# Optocoupler_module.net
KiCad netlist of a schematic drawn in Altium Designer
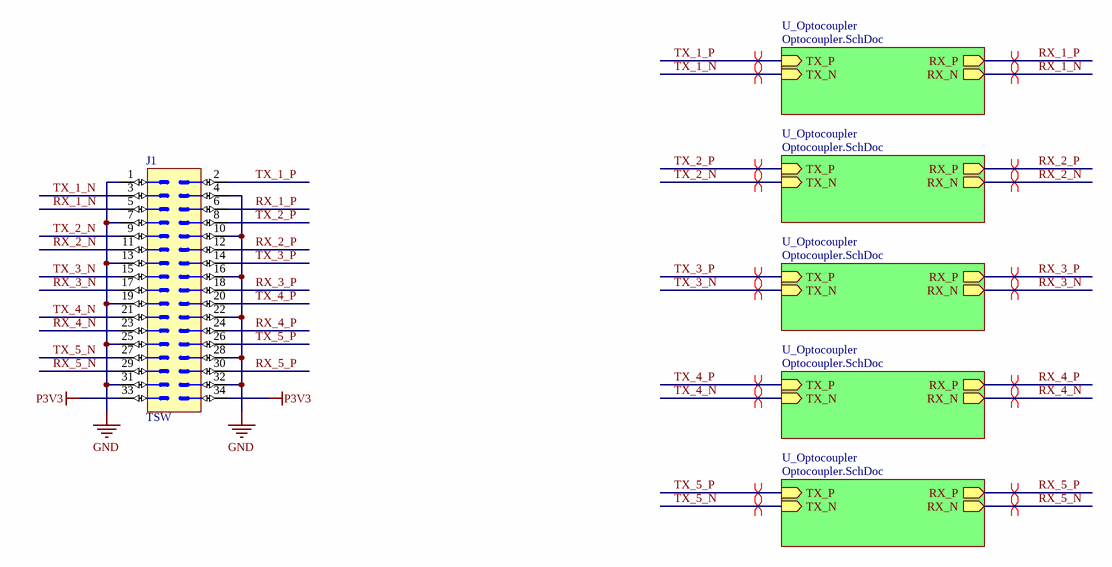
[diagram p0: Optocoupler_module.SchDoc]

(export (version "E")
  (design (tool "Eeschema 10.0.6"))
  (components
    (comp (ref "J1")
      (value "TSW")
      (footprint "SAMTEC_SW-117-08")
      (description "Connector 34 Male")
      (fields
        (field (name "PART NUMBER") "TSW-117-08-T-D-RA")
        (field (name "MANUFACTURER") "SAMTEC")
        (field (name "AUTHOR") "Michal Beldyga")
      )
      (libsource (lib "Connectors") (part "Connector 34 Male 2 Row"))
    )
  )
  (nets
    (net (code "1") (name "/RX_1_N") (class "Default")
      (node (ref "J1") (pin "5") (pinfunction "5_5") (pintype "bidirectional"))
    )
    (net (code "2") (name "/RX_1_P") (class "Default")
      (node (ref "J1") (pin "6") (pinfunction "6_6") (pintype "bidirectional"))
    )
    (net (code "3") (name "/RX_2_N") (class "Default")
      (node (ref "J1") (pin "11") (pinfunction "11_11") (pintype "bidirectional"))
    )
    (net (code "4") (name "/RX_2_P") (class "Default")
      (node (ref "J1") (pin "12") (pinfunction "12_12") (pintype "bidirectional"))
    )
    (net (code "5") (name "/RX_3_N") (class "Default")
      (node (ref "J1") (pin "17") (pinfunction "17_17") (pintype "bidirectional"))
    )
    (net (code "6") (name "/RX_3_P") (class "Default")
      (node (ref "J1") (pin "18") (pinfunction "18_18") (pintype "bidirectional"))
    )
    (net (code "7") (name "/RX_4_N") (class "Default")
      (node (ref "J1") (pin "23") (pinfunction "23_23") (pintype "bidirectional"))
    )
    (net (code "8") (name "/RX_4_P") (class "Default")
      (node (ref "J1") (pin "24") (pinfunction "24_24") (pintype "bidirectional"))
    )
    (net (code "9") (name "/RX_5_N") (class "Default")
      (node (ref "J1") (pin "29") (pinfunction "29_29") (pintype "bidirectional"))
    )
    (net (code "10") (name "/RX_5_P") (class "Default")
      (node (ref "J1") (pin "30") (pinfunction "30_30") (pintype "bidirectional"))
    )
    (net (code "11") (name "/TX_1_N") (class "Default")
      (node (ref "J1") (pin "3") (pinfunction "3_3") (pintype "bidirectional"))
    )
    (net (code "12") (name "/TX_1_P") (class "Default")
      (node (ref "J1") (pin "2") (pinfunction "2_2") (pintype "bidirectional"))
    )
    (net (code "13") (name "/TX_2_N") (class "Default")
      (node (ref "J1") (pin "9") (pinfunction "9_9") (pintype "bidirectional"))
    )
    (net (code "14") (name "/TX_2_P") (class "Default")
      (node (ref "J1") (pin "8") (pinfunction "8_8") (pintype "bidirectional"))
    )
    (net (code "15") (name "/TX_3_N") (class "Default")
      (node (ref "J1") (pin "15") (pinfunction "15_15") (pintype "bidirectional"))
    )
    (net (code "16") (name "/TX_3_P") (class "Default")
      (node (ref "J1") (pin "14") (pinfunction "14_14") (pintype "bidirectional"))
    )
    (net (code "17") (name "/TX_4_N") (class "Default")
      (node (ref "J1") (pin "21") (pinfunction "21_21") (pintype "bidirectional"))
    )
    (net (code "18") (name "/TX_4_P") (class "Default")
      (node (ref "J1") (pin "20") (pinfunction "20_20") (pintype "bidirectional"))
    )
    (net (code "19") (name "/TX_5_N") (class "Default")
      (node (ref "J1") (pin "27") (pinfunction "27_27") (pintype "bidirectional"))
    )
    (net (code "20") (name "/TX_5_P") (class "Default")
      (node (ref "J1") (pin "26") (pinfunction "26_26") (pintype "bidirectional"))
    )
    (net (code "21") (name "GND") (class "Default")
      (node (ref "J1") (pin "1") (pinfunction "1_1") (pintype "bidirectional"))
      (node (ref "J1") (pin "10") (pinfunction "10_10") (pintype "bidirectional"))
      (node (ref "J1") (pin "13") (pinfunction "13_13") (pintype "bidirectional"))
      (node (ref "J1") (pin "16") (pinfunction "16_16") (pintype "bidirectional"))
      (node (ref "J1") (pin "19") (pinfunction "19_19") (pintype "bidirectional"))
      (node (ref "J1") (pin "22") (pinfunction "22_22") (pintype "bidirectional"))
      (node (ref "J1") (pin "25") (pinfunction "25_25") (pintype "bidirectional"))
      (node (ref "J1") (pin "28") (pinfunction "28_28") (pintype "bidirectional"))
      (node (ref "J1") (pin "31") (pinfunction "31_31") (pintype "bidirectional"))
      (node (ref "J1") (pin "32") (pinfunction "32_32") (pintype "bidirectional"))
      (node (ref "J1") (pin "4") (pinfunction "4_4") (pintype "bidirectional"))
      (node (ref "J1") (pin "7") (pinfunction "7_7") (pintype "bidirectional"))
    )
    (net (code "22") (name "P3V3") (class "Default")
      (node (ref "J1") (pin "33") (pinfunction "33_33") (pintype "bidirectional"))
      (node (ref "J1") (pin "34") (pinfunction "34_34") (pintype "bidirectional"))
    )
  )
)
